# MOSFET_PowerControlKit.net
KiCad netlist of a schematic drawn in EAGLE
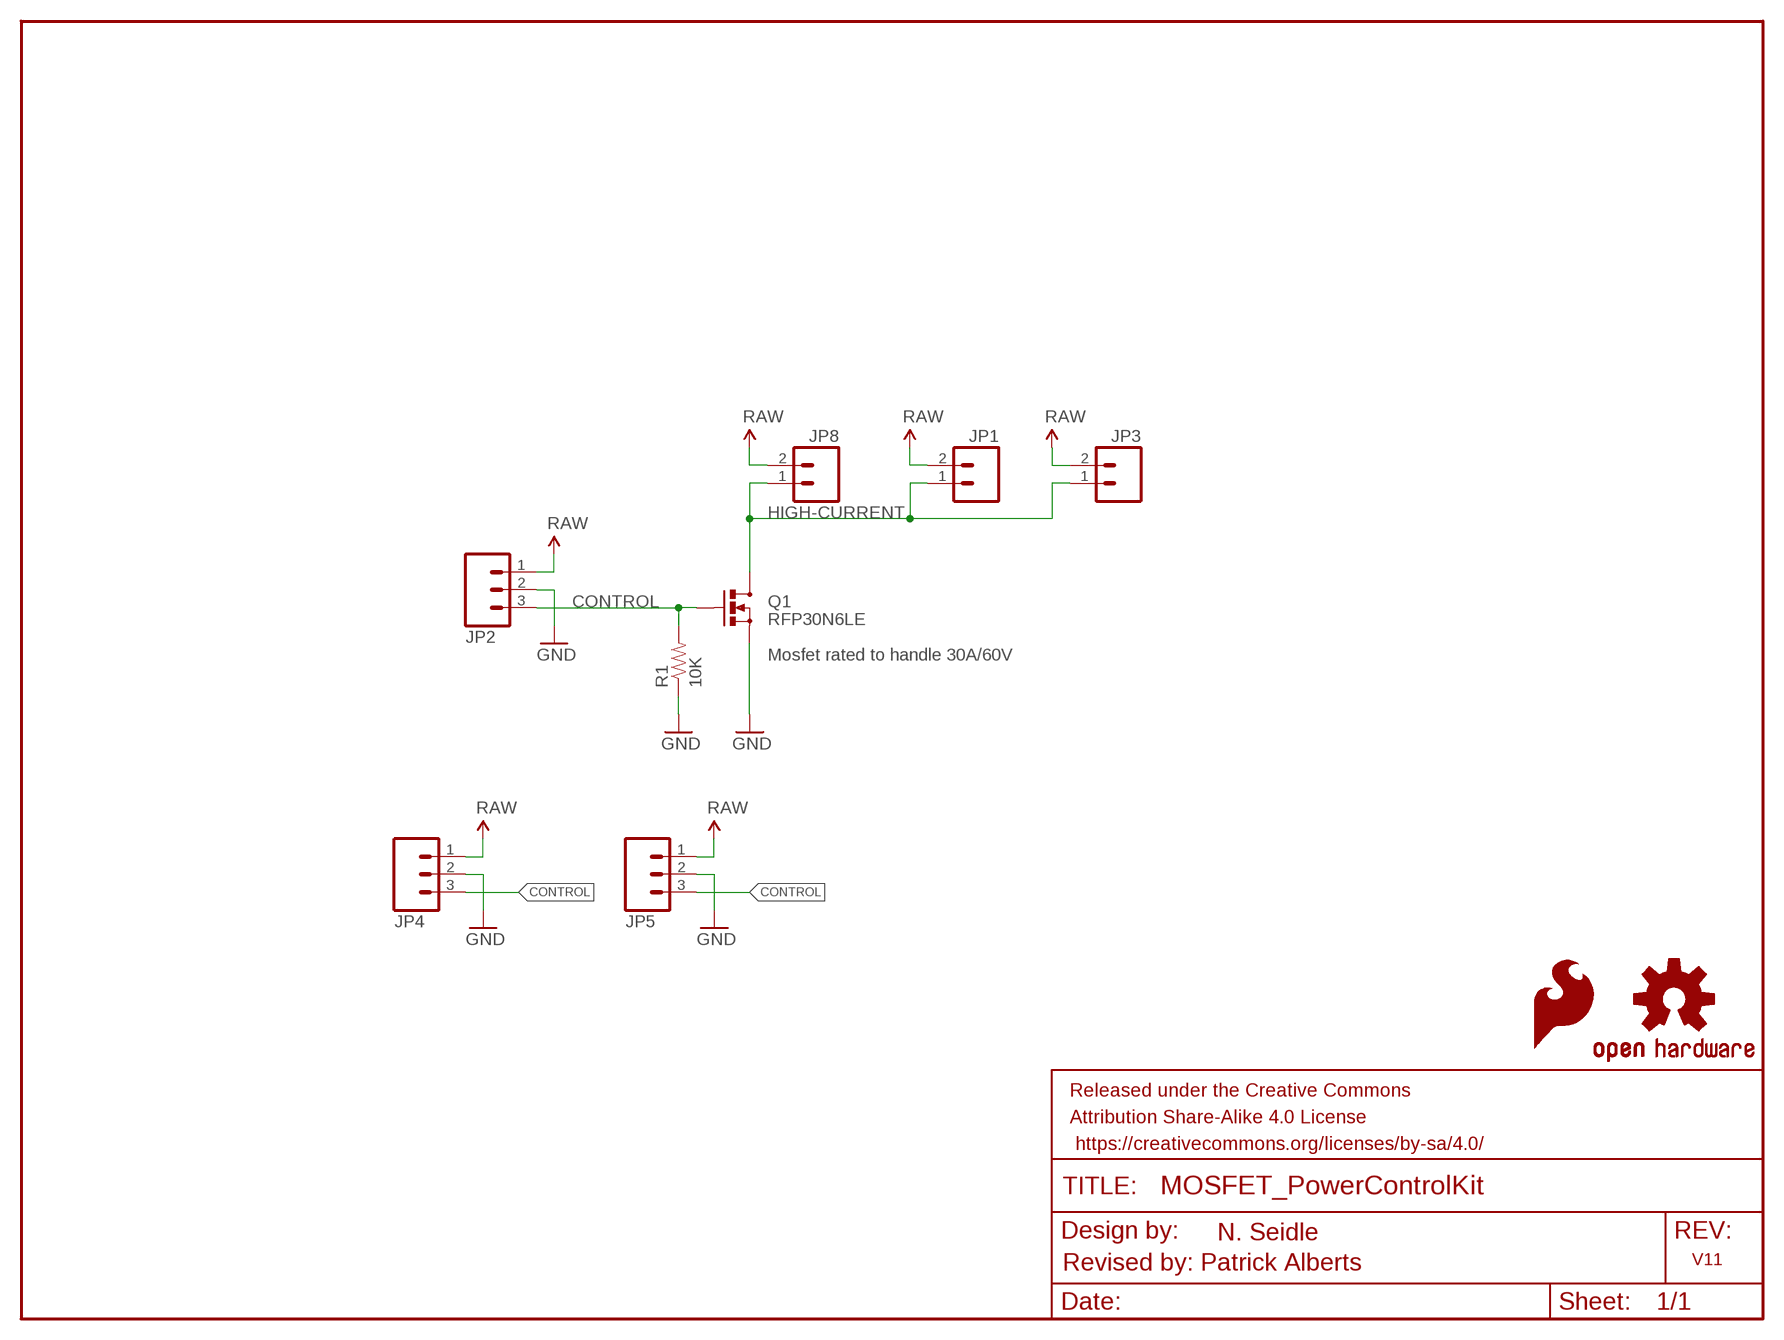
[diagram p0: schematic, sheet 1]

(export (version "E")
  (design (tool "Eeschema 10.0.6"))
  (components
    (comp (ref "FRAME1")
      (value "FRAME-LETTER")
      (footprint "eagle-import:CREATIVE_COMMONS")
      (libsource (lib "eagle-import") (part "FRAME-LETTER"))
    )
    (comp (ref "JP1")
      (value "M023.5MM")
      (footprint "eagle-import:SCREWTERMINAL-3.5MM-2")
      (libsource (lib "eagle-import") (part "M023.5MM"))
    )
    (comp (ref "JP2")
      (value "M03JST-PTH")
      (footprint "eagle-import:JST-3-PTH")
      (libsource (lib "eagle-import") (part "M03JST-PTH"))
    )
    (comp (ref "JP3")
      (value "M02PTH")
      (footprint "eagle-import:1X02")
      (libsource (lib "eagle-import") (part "SparkFun-Connectors_M02PTH"))
    )
    (comp (ref "JP4")
      (value "M03SCREW")
      (footprint "eagle-import:SCREWTERMINAL-3.5MM-3")
      (libsource (lib "eagle-import") (part "M03SCREW"))
    )
    (comp (ref "JP5")
      (value "M03PTH")
      (footprint "eagle-import:1X03")
      (libsource (lib "eagle-import") (part "M03PTH"))
    )
    (comp (ref "JP8")
      (value "M02JST-PTH-2")
      (footprint "eagle-import:JST-2-PTH")
      (libsource (lib "eagle-import") (part "M02JST-PTH-2"))
    )
    (comp (ref "LOGO1")
      (value "OSHW-LOGOS")
      (footprint "eagle-import:OSHW-LOGO-S")
      (libsource (lib "eagle-import") (part "OSHW-LOGOS"))
    )
    (comp (ref "LOGO2")
      (value "SFE_LOGO_FLAME.1_INCH")
      (footprint "eagle-import:SFE_LOGO_FLAME_.1")
      (libsource (lib "eagle-import") (part "SFE_LOGO_FLAME.1_INCH"))
    )
    (comp (ref "Q1")
      (value "RFP30N6LE")
      (footprint "eagle-import:TO220V")
      (libsource (lib "eagle-import") (part "MOSFET-NCHANNELPTH2"))
    )
    (comp (ref "R1")
      (value "10K")
      (footprint "eagle-import:AXIAL-0.3")
      (libsource (lib "eagle-import") (part "RESISTORPTH1"))
    )
  )
  (nets
    (net (code "1") (name "/HIGH-CURRENT") (class "Default")
      (node (ref "JP1") (pin "1") (pinfunction "1_1") (pintype "passive"))
      (node (ref "JP3") (pin "1") (pinfunction "1_1") (pintype "passive"))
      (node (ref "JP8") (pin "1") (pinfunction "1_1") (pintype "passive"))
      (node (ref "Q1") (pin "2") (pinfunction "D_2") (pintype "passive"))
    )
    (net (code "2") (name "CONTROL") (class "Default")
      (node (ref "JP2") (pin "3") (pinfunction "3_3") (pintype "passive"))
      (node (ref "JP4") (pin "3") (pinfunction "3_3") (pintype "passive"))
      (node (ref "JP5") (pin "3") (pinfunction "3_3") (pintype "passive"))
      (node (ref "Q1") (pin "1") (pinfunction "G_1") (pintype "passive"))
      (node (ref "R1") (pin "P$2") (pinfunction "2_P$2") (pintype "passive"))
    )
    (net (code "3") (name "GND") (class "Default")
      (node (ref "JP2") (pin "2") (pinfunction "2_2") (pintype "passive"))
      (node (ref "JP4") (pin "2") (pinfunction "2_2") (pintype "passive"))
      (node (ref "JP5") (pin "2") (pinfunction "2_2") (pintype "passive"))
      (node (ref "Q1") (pin "3") (pinfunction "S_3") (pintype "passive"))
      (node (ref "R1") (pin "P$1") (pinfunction "1_P$1") (pintype "passive"))
    )
    (net (code "4") (name "RAW") (class "Default")
      (node (ref "JP1") (pin "2") (pinfunction "2_2") (pintype "passive"))
      (node (ref "JP2") (pin "1") (pinfunction "1_1") (pintype "passive"))
      (node (ref "JP3") (pin "2") (pinfunction "2_2") (pintype "passive"))
      (node (ref "JP4") (pin "1") (pinfunction "1_1") (pintype "passive"))
      (node (ref "JP5") (pin "1") (pinfunction "1_1") (pintype "passive"))
      (node (ref "JP8") (pin "2") (pinfunction "2_2") (pintype "passive"))
    )
  )
)
